# rfid_ctl3.net
KiCad netlist of a schematic drawn in EAGLE
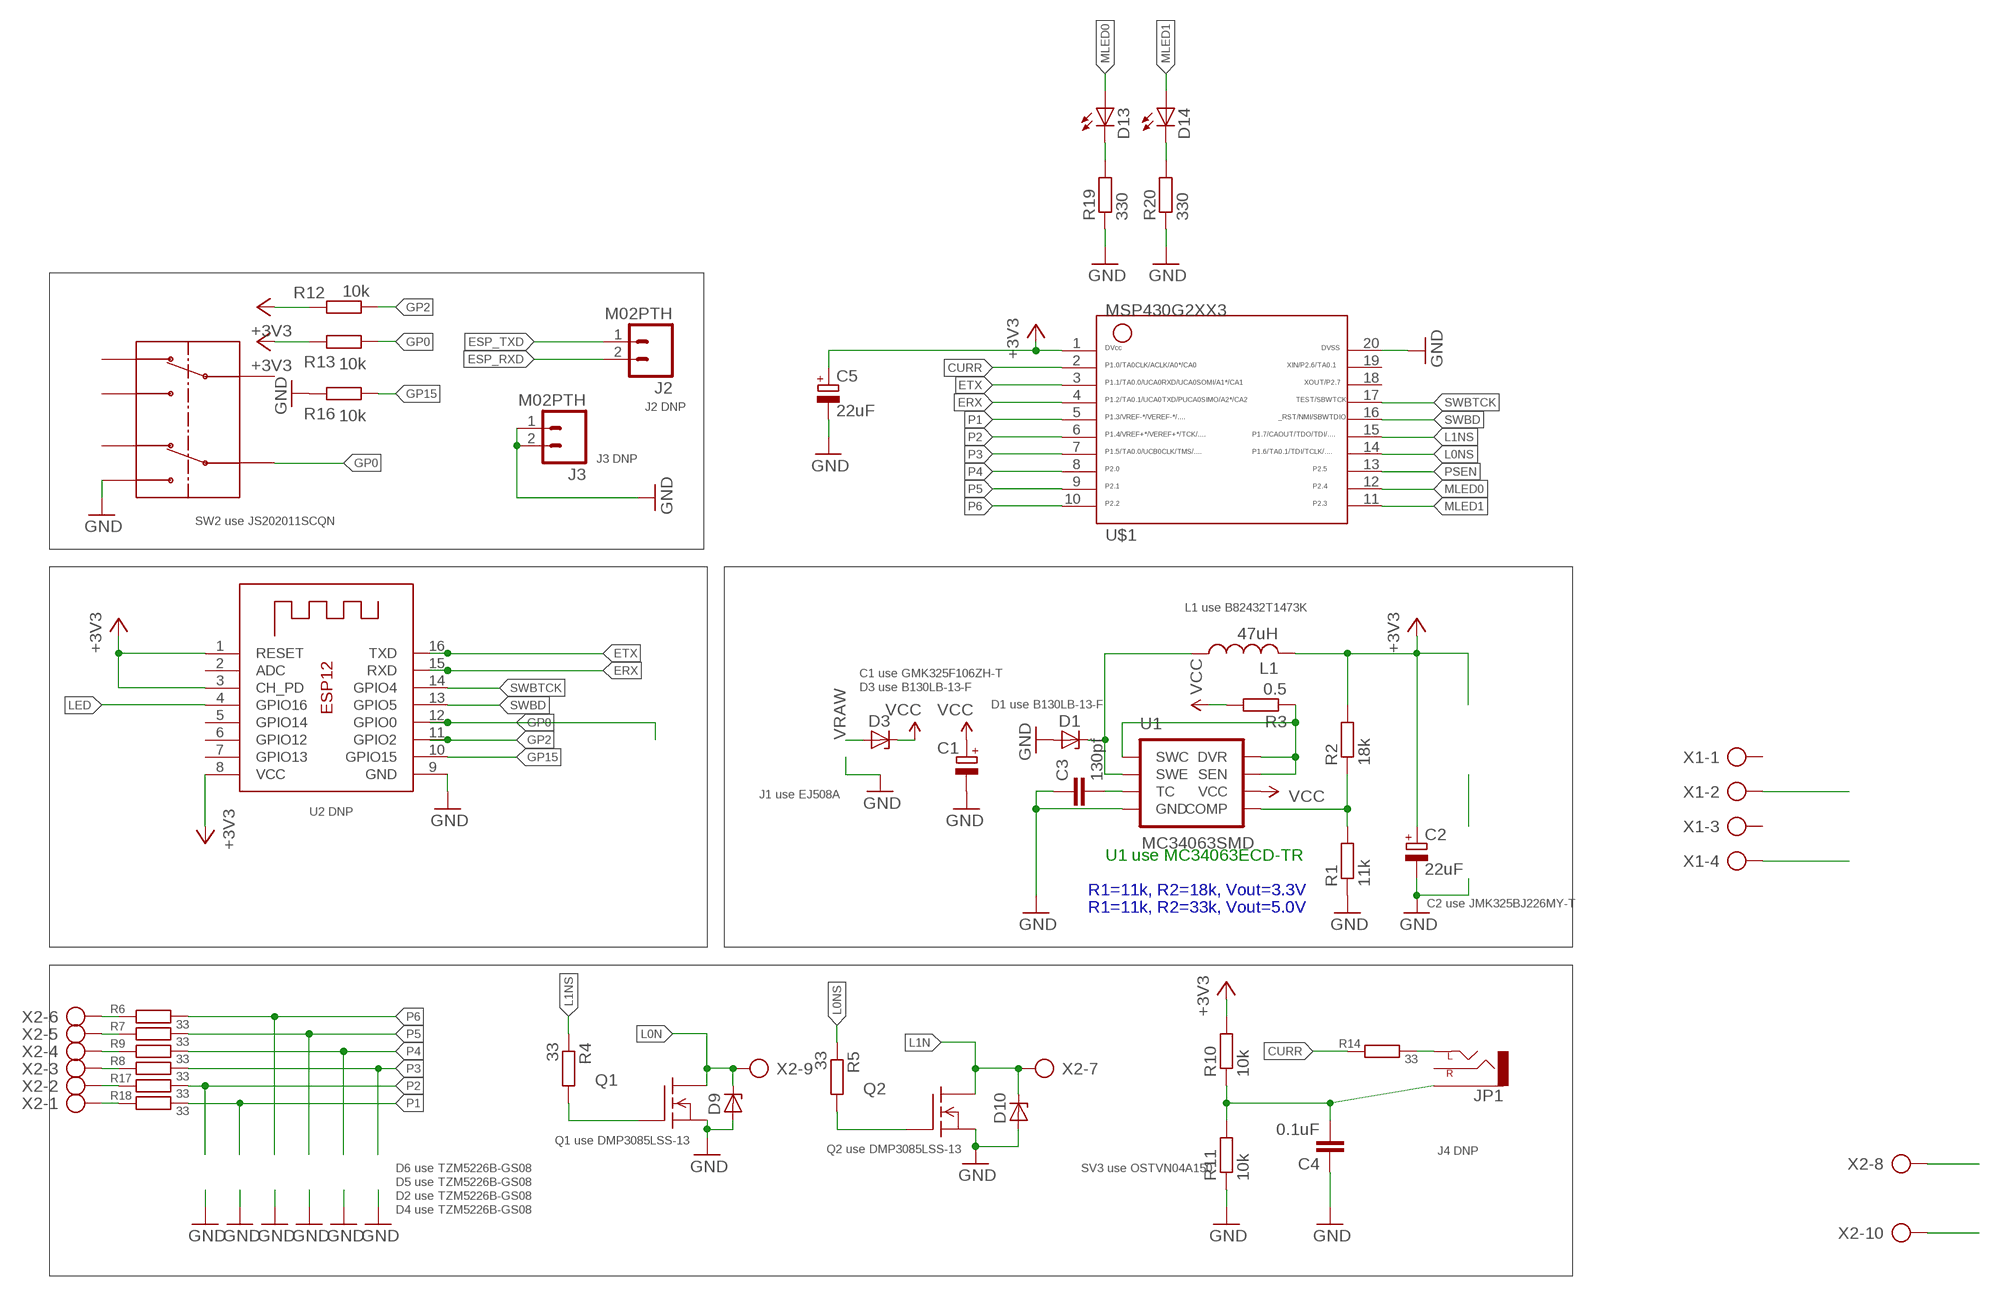
[diagram p0: schematic, sheet 1]

(export (version "E")
  (design (tool "Eeschema 10.0.6"))
  (components
    (comp (ref "C1")
      (value "CPOL-EUE2.5-7")
      (footprint "eagle-import:E2,5-7")
      (libsource (lib "eagle-import") (part "CPOL-EUE2.5-7"))
    )
    (comp (ref "C2")
      (value "22uF")
      (footprint "eagle-import:E2,5-7")
      (libsource (lib "eagle-import") (part "CPOL-EUE2.5-7"))
    )
    (comp (ref "C3")
      (value "130pf")
      (footprint "eagle-import:C1206")
      (libsource (lib "eagle-import") (part "C-EUC1206"))
    )
    (comp (ref "C4")
      (value "0.1uF")
      (footprint "eagle-import:C0603")
      (libsource (lib "eagle-import") (part "C-EUC0603"))
    )
    (comp (ref "C5")
      (value "22uF")
      (footprint "eagle-import:E1,8-4")
      (libsource (lib "eagle-import") (part "CPOL-EUE1.8-4"))
    )
    (comp (ref "D1")
      (value "ZENER-DIODESMB")
      (footprint "eagle-import:SMB")
      (libsource (lib "eagle-import") (part "ZENER-DIODESMB"))
    )
    (comp (ref "D3")
      (value "ZENER-DIODESMB")
      (footprint "eagle-import:SMB")
      (libsource (lib "eagle-import") (part "ZENER-DIODESMB"))
    )
    (comp (ref "D9")
      (value "ZENER-DIODESMB")
      (footprint "eagle-import:SMB")
      (libsource (lib "eagle-import") (part "ZENER-DIODESMB"))
    )
    (comp (ref "D10")
      (value "ZENER-DIODESMB")
      (footprint "eagle-import:SMB")
      (libsource (lib "eagle-import") (part "ZENER-DIODESMB"))
    )
    (comp (ref "D13")
      (value "LED5MM")
      (footprint "eagle-import:LED5MM")
      (libsource (lib "eagle-import") (part "LED5MM"))
    )
    (comp (ref "D14")
      (value "LED5MM")
      (footprint "eagle-import:LED5MM")
      (libsource (lib "eagle-import") (part "LED5MM"))
    )
    (comp (ref "J2")
      (value "M02PTH")
      (footprint "eagle-import:1X02")
      (libsource (lib "eagle-import") (part "M02PTH"))
    )
    (comp (ref "J3")
      (value "M02PTH")
      (footprint "eagle-import:1X02")
      (libsource (lib "eagle-import") (part "M02PTH"))
    )
    (comp (ref "JP1")
      (value "AUDIO-JACKSMD2")
      (footprint "eagle-import:AUDIO-JACK-3.5MM-SMD")
      (libsource (lib "eagle-import") (part "AUDIO-JACKSMD2"))
    )
    (comp (ref "L1")
      (value "47uH")
      (footprint "eagle-import:L1812")
      (libsource (lib "eagle-import") (part "L-USL1812"))
    )
    (comp (ref "Q1")
      (value "FDS5680")
      (footprint "eagle-import:SO-8")
      (libsource (lib "eagle-import") (part "FDS5680"))
    )
    (comp (ref "Q2")
      (value "FDS5680")
      (footprint "eagle-import:SO-8")
      (libsource (lib "eagle-import") (part "FDS5680"))
    )
    (comp (ref "R1")
      (value "11k")
      (footprint "eagle-import:R1206")
      (libsource (lib "eagle-import") (part "R-EU_R1206"))
    )
    (comp (ref "R2")
      (value "18k")
      (footprint "eagle-import:R1206")
      (libsource (lib "eagle-import") (part "R-EU_R1206"))
    )
    (comp (ref "R3")
      (value "0.5")
      (footprint "eagle-import:R1206")
      (libsource (lib "eagle-import") (part "R-EU_R1206"))
    )
    (comp (ref "R4")
      (value "33")
      (footprint "eagle-import:R1206")
      (libsource (lib "eagle-import") (part "R-EU_R1206"))
    )
    (comp (ref "R5")
      (value "33")
      (footprint "eagle-import:R1206")
      (libsource (lib "eagle-import") (part "R-EU_R1206"))
    )
    (comp (ref "R6")
      (value "33")
      (footprint "eagle-import:R1206")
      (libsource (lib "eagle-import") (part "R-EU_R1206"))
    )
    (comp (ref "R7")
      (value "33")
      (footprint "eagle-import:R1206")
      (libsource (lib "eagle-import") (part "R-EU_R1206"))
    )
    (comp (ref "R8")
      (value "33")
      (footprint "eagle-import:R1206")
      (libsource (lib "eagle-import") (part "R-EU_R1206"))
    )
    (comp (ref "R9")
      (value "33")
      (footprint "eagle-import:R1206")
      (libsource (lib "eagle-import") (part "R-EU_R1206"))
    )
    (comp (ref "R10")
      (value "10k")
      (footprint "eagle-import:R0603")
      (libsource (lib "eagle-import") (part "R-EU_R0603"))
    )
    (comp (ref "R11")
      (value "10k")
      (footprint "eagle-import:R0603")
      (libsource (lib "eagle-import") (part "R-EU_R0603"))
    )
    (comp (ref "R12")
      (value "10k")
      (footprint "eagle-import:R1206")
      (libsource (lib "eagle-import") (part "R-EU_R1206"))
    )
    (comp (ref "R13")
      (value "10k")
      (footprint "eagle-import:R1206")
      (libsource (lib "eagle-import") (part "R-EU_R1206"))
    )
    (comp (ref "R14")
      (value "33")
      (footprint "eagle-import:R1206")
      (libsource (lib "eagle-import") (part "R-EU_R1206"))
    )
    (comp (ref "R16")
      (value "10k")
      (footprint "eagle-import:R0603")
      (libsource (lib "eagle-import") (part "R-EU_R0603"))
    )
    (comp (ref "R17")
      (value "33")
      (footprint "eagle-import:R1206")
      (libsource (lib "eagle-import") (part "R-EU_R1206"))
    )
    (comp (ref "R18")
      (value "33")
      (footprint "eagle-import:R1206")
      (libsource (lib "eagle-import") (part "R-EU_R1206"))
    )
    (comp (ref "R19")
      (value "330")
      (footprint "eagle-import:R0805")
      (libsource (lib "eagle-import") (part "R-EU_R0805"))
    )
    (comp (ref "R20")
      (value "330")
      (footprint "eagle-import:R0805")
      (libsource (lib "eagle-import") (part "R-EU_R0805"))
    )
    (comp (ref "SW2")
      (value "L202011MS02Q")
      (footprint "eagle-import:SMT")
      (libsource (lib "eagle-import") (part "L202011MS02Q"))
    )
    (comp (ref "U$1")
      (value "G2XX3---N20")
      (footprint "eagle-import:N20")
      (libsource (lib "eagle-import") (part "G2XX3---N20"))
    )
    (comp (ref "U1")
      (value "MC34063SMD")
      (footprint "eagle-import:SO08")
      (libsource (lib "eagle-import") (part "MC34063SMD"))
    )
    (comp (ref "U2")
      (value "ESP-12")
      (footprint "eagle-import:ESP-12")
      (libsource (lib "eagle-import") (part "ESP-12"))
    )
    (comp (ref "X1")
      (value "AK300/4")
      (footprint "eagle-import:AK300_4")
      (libsource (lib "eagle-import") (part "AK300/4"))
    )
    (comp (ref "X2")
      (value "AK300/10")
      (footprint "eagle-import:AK300_10")
      (libsource (lib "eagle-import") (part "AK300/10"))
    )
  )
  (nets
    (net (code "1") (name "+3V3") (class "Default")
      (node (ref "C2") (pin "+") (pinfunction "+_+") (pintype "passive"))
      (node (ref "C5") (pin "+") (pinfunction "+_+") (pintype "passive"))
      (node (ref "L1") (pin "2") (pinfunction "2_2") (pintype "passive"))
      (node (ref "R10") (pin "2") (pinfunction "2_2") (pintype "passive"))
      (node (ref "R12") (pin "2") (pinfunction "2_2") (pintype "passive"))
      (node (ref "R13") (pin "2") (pinfunction "2_2") (pintype "passive"))
      (node (ref "R2") (pin "2") (pinfunction "2_2") (pintype "passive"))
      (node (ref "U$1") (pin "1") (pinfunction "1_1") (pintype "bidirectional"))
      (node (ref "U2") (pin "1") (pinfunction "RESET_1") (pintype "input"))
      (node (ref "U2") (pin "3") (pinfunction "CH_PD_3") (pintype "input"))
      (node (ref "U2") (pin "8") (pinfunction "VCC_8") (pintype "power_in"))
    )
    (net (code "2") (name "/VRAW") (class "Default")
      (node (ref "D3") (pin "A") (pinfunction "A_A") (pintype "passive"))
      (node (ref "X1") (pin "2") (pinfunction "KL_2") (pintype "passive"))
      (node (ref "X1") (pin "4") (pinfunction "KL_4") (pintype "passive"))
      (node (ref "X2") (pin "10") (pinfunction "KL_10") (pintype "passive"))
      (node (ref "X2") (pin "8") (pinfunction "KL_8") (pintype "passive"))
    )
    (net (code "3") (name "CURR") (class "Default")
      (node (ref "R14") (pin "1") (pinfunction "1_1") (pintype "passive"))
      (node (ref "U$1") (pin "2") (pinfunction "2_2") (pintype "bidirectional"))
    )
    (net (code "4") (name "ERX") (class "Default")
      (node (ref "U$1") (pin "4") (pinfunction "4_4") (pintype "bidirectional"))
      (node (ref "U2") (pin "15") (pinfunction "RXD_15") (pintype "input"))
    )
    (net (code "5") (name "ESP_RXD") (class "Default")
      (node (ref "J2") (pin "2") (pinfunction "2_2") (pintype "passive"))
    )
    (net (code "6") (name "ESP_TXD") (class "Default")
      (node (ref "J2") (pin "1") (pinfunction "1_1") (pintype "passive"))
    )
    (net (code "7") (name "ETX") (class "Default")
      (node (ref "U$1") (pin "3") (pinfunction "3_3") (pintype "bidirectional"))
      (node (ref "U2") (pin "16") (pinfunction "TXD_16") (pintype "output"))
    )
    (net (code "8") (name "GND") (class "Default")
      (node (ref "C1") (pin "-") (pinfunction "-_-") (pintype "passive"))
      (node (ref "C2") (pin "-") (pinfunction "-_-") (pintype "passive"))
      (node (ref "C3") (pin "1") (pinfunction "1_1") (pintype "passive"))
      (node (ref "C4") (pin "1") (pinfunction "1_1") (pintype "passive"))
      (node (ref "C5") (pin "-") (pinfunction "-_-") (pintype "passive"))
      (node (ref "D1") (pin "A") (pinfunction "A_A") (pintype "passive"))
      (node (ref "D10") (pin "A") (pinfunction "A_A") (pintype "passive"))
      (node (ref "D9") (pin "A") (pinfunction "A_A") (pintype "passive"))
      (node (ref "J3") (pin "1") (pinfunction "1_1") (pintype "passive"))
      (node (ref "J3") (pin "2") (pinfunction "2_2") (pintype "passive"))
      (node (ref "Q1") (pin "1") (pinfunction "S_1") (pintype "passive"))
      (node (ref "Q1") (pin "2") (pinfunction "S_2") (pintype "passive"))
      (node (ref "Q1") (pin "3") (pinfunction "S_3") (pintype "passive"))
      (node (ref "Q2") (pin "1") (pinfunction "S_1") (pintype "passive"))
      (node (ref "Q2") (pin "2") (pinfunction "S_2") (pintype "passive"))
      (node (ref "Q2") (pin "3") (pinfunction "S_3") (pintype "passive"))
      (node (ref "R1") (pin "1") (pinfunction "1_1") (pintype "passive"))
      (node (ref "R11") (pin "1") (pinfunction "1_1") (pintype "passive"))
      (node (ref "R16") (pin "2") (pinfunction "2_2") (pintype "passive"))
      (node (ref "R19") (pin "1") (pinfunction "1_1") (pintype "passive"))
      (node (ref "R20") (pin "1") (pinfunction "1_1") (pintype "passive"))
      (node (ref "SW2") (pin "B1") (pinfunction "B1_B1") (pintype "bidirectional"))
      (node (ref "U$1") (pin "20") (pinfunction "20_20") (pintype "bidirectional"))
      (node (ref "U1") (pin "4") (pinfunction "GND_4") (pintype "bidirectional"))
      (node (ref "U2") (pin "9") (pinfunction "GND_9") (pintype "power_in"))
    )
    (net (code "9") (name "GP0") (class "Default")
      (node (ref "R13") (pin "1") (pinfunction "1_1") (pintype "passive"))
      (node (ref "SW2") (pin "B") (pinfunction "B_B") (pintype "bidirectional"))
      (node (ref "U2") (pin "12") (pinfunction "GPIO0_12") (pintype "bidirectional"))
    )
    (net (code "10") (name "GP2") (class "Default")
      (node (ref "R12") (pin "1") (pinfunction "1_1") (pintype "passive"))
      (node (ref "U2") (pin "11") (pinfunction "GPIO2_11") (pintype "bidirectional"))
    )
    (net (code "11") (name "GP15") (class "Default")
      (node (ref "R16") (pin "1") (pinfunction "1_1") (pintype "passive"))
      (node (ref "U2") (pin "10") (pinfunction "GPIO15_10") (pintype "bidirectional"))
    )
    (net (code "12") (name "L0N") (class "Default")
      (node (ref "D9") (pin "C") (pinfunction "C_C") (pintype "passive"))
      (node (ref "Q1") (pin "5") (pinfunction "D_5") (pintype "passive"))
      (node (ref "Q1") (pin "6") (pinfunction "D_6") (pintype "passive"))
      (node (ref "Q1") (pin "7") (pinfunction "D_7") (pintype "passive"))
      (node (ref "Q1") (pin "8") (pinfunction "D_8") (pintype "passive"))
      (node (ref "X2") (pin "9") (pinfunction "KL_9") (pintype "passive"))
    )
    (net (code "13") (name "L0NS") (class "Default")
      (node (ref "R5") (pin "1") (pinfunction "1_1") (pintype "passive"))
      (node (ref "U$1") (pin "14") (pinfunction "14_14") (pintype "bidirectional"))
    )
    (net (code "14") (name "L1N") (class "Default")
      (node (ref "D10") (pin "C") (pinfunction "C_C") (pintype "passive"))
      (node (ref "Q2") (pin "5") (pinfunction "D_5") (pintype "passive"))
      (node (ref "Q2") (pin "6") (pinfunction "D_6") (pintype "passive"))
      (node (ref "Q2") (pin "7") (pinfunction "D_7") (pintype "passive"))
      (node (ref "Q2") (pin "8") (pinfunction "D_8") (pintype "passive"))
      (node (ref "X2") (pin "7") (pinfunction "KL_7") (pintype "passive"))
    )
    (net (code "15") (name "L1NS") (class "Default")
      (node (ref "R4") (pin "1") (pinfunction "1_1") (pintype "passive"))
      (node (ref "U$1") (pin "15") (pinfunction "15_15") (pintype "bidirectional"))
    )
    (net (code "16") (name "LED") (class "Default")
      (node (ref "U2") (pin "4") (pinfunction "GPIO16_4") (pintype "bidirectional"))
    )
    (net (code "17") (name "MLED0") (class "Default")
      (node (ref "D13") (pin "A") (pinfunction "A_A") (pintype "passive"))
      (node (ref "U$1") (pin "12") (pinfunction "12_12") (pintype "bidirectional"))
    )
    (net (code "18") (name "MLED1") (class "Default")
      (node (ref "D14") (pin "A") (pinfunction "A_A") (pintype "passive"))
      (node (ref "U$1") (pin "11") (pinfunction "11_11") (pintype "bidirectional"))
    )
    (net (code "19") (name "Net-(C4-Pad2)") (class "Default")
      (node (ref "C4") (pin "2") (pinfunction "2_2") (pintype "passive"))
      (node (ref "JP1") (pin "SLEEVE") (pinfunction "SLEEVE_SLEEVE") (pintype "bidirectional"))
      (node (ref "R10") (pin "1") (pinfunction "1_1") (pintype "passive"))
      (node (ref "R11") (pin "2") (pinfunction "2_2") (pintype "passive"))
    )
    (net (code "20") (name "Net-(D13-C)") (class "Default")
      (node (ref "D13") (pin "K") (pinfunction "C_K") (pintype "passive"))
      (node (ref "R19") (pin "2") (pinfunction "2_2") (pintype "passive"))
    )
    (net (code "21") (name "Net-(D14-C)") (class "Default")
      (node (ref "D14") (pin "K") (pinfunction "C_K") (pintype "passive"))
      (node (ref "R20") (pin "2") (pinfunction "2_2") (pintype "passive"))
    )
    (net (code "22") (name "Net-(JP1-LEFT)") (class "Default")
      (node (ref "JP1") (pin "TIP") (pinfunction "LEFT_TIP") (pintype "bidirectional"))
      (node (ref "R14") (pin "2") (pinfunction "2_2") (pintype "passive"))
    )
    (net (code "23") (name "Net-(Q1-G)") (class "Default")
      (node (ref "Q1") (pin "4") (pinfunction "G_4") (pintype "passive"))
      (node (ref "R4") (pin "2") (pinfunction "2_2") (pintype "passive"))
    )
    (net (code "24") (name "Net-(Q2-G)") (class "Default")
      (node (ref "Q2") (pin "4") (pinfunction "G_4") (pintype "passive"))
      (node (ref "R5") (pin "2") (pinfunction "2_2") (pintype "passive"))
    )
    (net (code "25") (name "Net-(U1-COMP)") (class "Default")
      (node (ref "R1") (pin "2") (pinfunction "2_2") (pintype "passive"))
      (node (ref "R2") (pin "1") (pinfunction "1_1") (pintype "passive"))
      (node (ref "U1") (pin "5") (pinfunction "COMP_5") (pintype "bidirectional"))
    )
    (net (code "26") (name "Net-(U1-DVR)") (class "Default")
      (node (ref "R3") (pin "1") (pinfunction "1_1") (pintype "passive"))
      (node (ref "U1") (pin "1") (pinfunction "SWC_1") (pintype "bidirectional"))
      (node (ref "U1") (pin "7") (pinfunction "SEN_7") (pintype "bidirectional"))
      (node (ref "U1") (pin "8") (pinfunction "DVR_8") (pintype "bidirectional"))
    )
    (net (code "27") (name "Net-(U1-SWE)") (class "Default")
      (node (ref "D1") (pin "C") (pinfunction "C_C") (pintype "passive"))
      (node (ref "L1") (pin "1") (pinfunction "1_1") (pintype "passive"))
      (node (ref "U1") (pin "2") (pinfunction "SWE_2") (pintype "bidirectional"))
    )
    (net (code "28") (name "Net-(U1-TC)") (class "Default")
      (node (ref "C3") (pin "2") (pinfunction "2_2") (pintype "passive"))
      (node (ref "U1") (pin "3") (pinfunction "TC_3") (pintype "bidirectional"))
    )
    (net (code "29") (name "Net-(X2A-KL)") (class "Default")
      (node (ref "R18") (pin "1") (pinfunction "1_1") (pintype "passive"))
      (node (ref "X2") (pin "1") (pinfunction "KL_1") (pintype "passive"))
    )
    (net (code "30") (name "Net-(X2C-KL)") (class "Default")
      (node (ref "R17") (pin "1") (pinfunction "1_1") (pintype "passive"))
      (node (ref "X2") (pin "2") (pinfunction "KL_2") (pintype "passive"))
    )
    (net (code "31") (name "Net-(X2D-KL)") (class "Default")
      (node (ref "R9") (pin "1") (pinfunction "1_1") (pintype "passive"))
      (node (ref "X2") (pin "3") (pinfunction "KL_3") (pintype "passive"))
    )
    (net (code "32") (name "Net-(X2E-KL)") (class "Default")
      (node (ref "R8") (pin "1") (pinfunction "1_1") (pintype "passive"))
      (node (ref "X2") (pin "4") (pinfunction "KL_4") (pintype "passive"))
    )
    (net (code "33") (name "Net-(X2F-KL)") (class "Default")
      (node (ref "R7") (pin "1") (pinfunction "1_1") (pintype "passive"))
      (node (ref "X2") (pin "5") (pinfunction "KL_5") (pintype "passive"))
    )
    (net (code "34") (name "Net-(X2G-KL)") (class "Default")
      (node (ref "R6") (pin "1") (pinfunction "1_1") (pintype "passive"))
      (node (ref "X2") (pin "6") (pinfunction "KL_6") (pintype "passive"))
    )
    (net (code "35") (name "P1") (class "Default")
      (node (ref "R18") (pin "2") (pinfunction "2_2") (pintype "passive"))
      (node (ref "U$1") (pin "5") (pinfunction "5_5") (pintype "bidirectional"))
    )
    (net (code "36") (name "P2") (class "Default")
      (node (ref "R17") (pin "2") (pinfunction "2_2") (pintype "passive"))
      (node (ref "U$1") (pin "6") (pinfunction "6_6") (pintype "bidirectional"))
    )
    (net (code "37") (name "P3") (class "Default")
      (node (ref "R9") (pin "2") (pinfunction "2_2") (pintype "passive"))
      (node (ref "U$1") (pin "7") (pinfunction "7_7") (pintype "bidirectional"))
    )
    (net (code "38") (name "P4") (class "Default")
      (node (ref "R8") (pin "2") (pinfunction "2_2") (pintype "passive"))
      (node (ref "U$1") (pin "8") (pinfunction "8_8") (pintype "bidirectional"))
    )
    (net (code "39") (name "P5") (class "Default")
      (node (ref "R7") (pin "2") (pinfunction "2_2") (pintype "passive"))
      (node (ref "U$1") (pin "9") (pinfunction "9_9") (pintype "bidirectional"))
    )
    (net (code "40") (name "P6") (class "Default")
      (node (ref "R6") (pin "2") (pinfunction "2_2") (pintype "passive"))
      (node (ref "U$1") (pin "10") (pinfunction "10_10") (pintype "bidirectional"))
    )
    (net (code "41") (name "PSEN") (class "Default")
      (node (ref "U$1") (pin "13") (pinfunction "13_13") (pintype "bidirectional"))
    )
    (net (code "42") (name "SWBD") (class "Default")
      (node (ref "U$1") (pin "16") (pinfunction "16_16") (pintype "bidirectional"))
      (node (ref "U2") (pin "13") (pinfunction "GPIO5_13") (pintype "bidirectional"))
    )
    (net (code "43") (name "SWBTCK") (class "Default")
      (node (ref "U$1") (pin "17") (pinfunction "17_17") (pintype "bidirectional"))
      (node (ref "U2") (pin "14") (pinfunction "GPIO4_14") (pintype "bidirectional"))
    )
    (net (code "44") (name "VCC") (class "Default")
      (node (ref "C1") (pin "+") (pinfunction "+_+") (pintype "passive"))
      (node (ref "D3") (pin "C") (pinfunction "C_C") (pintype "passive"))
      (node (ref "R3") (pin "2") (pinfunction "2_2") (pintype "passive"))
      (node (ref "U1") (pin "6") (pinfunction "VCC_6") (pintype "bidirectional"))
    )
    (net (code "45") (name "unconnected-(JP1-RIGHT-PadRING)") (class "Default")
      (node (ref "JP1") (pin "RING") (pinfunction "RIGHT_RING") (pintype "bidirectional"))
    )
    (net (code "46") (name "unconnected-(SW2-PadA)") (class "Default")
      (node (ref "SW2") (pin "A") (pinfunction "A_A") (pintype "bidirectional"))
    )
    (net (code "47") (name "unconnected-(SW2-PadA1)") (class "Default")
      (node (ref "SW2") (pin "A1") (pinfunction "A1_A1") (pintype "bidirectional"))
    )
    (net (code "48") (name "unconnected-(SW2-PadA2)") (class "Default")
      (node (ref "SW2") (pin "A2") (pinfunction "A2_A2") (pintype "bidirectional"))
    )
    (net (code "49") (name "unconnected-(SW2-PadB2)") (class "Default")
      (node (ref "SW2") (pin "B2") (pinfunction "B2_B2") (pintype "bidirectional"))
    )
    (net (code "50") (name "unconnected-(U$1-Pad18)") (class "Default")
      (node (ref "U$1") (pin "18") (pinfunction "18_18") (pintype "bidirectional"))
    )
    (net (code "51") (name "unconnected-(U$1-Pad19)") (class "Default")
      (node (ref "U$1") (pin "19") (pinfunction "19_19") (pintype "bidirectional"))
    )
    (net (code "52") (name "unconnected-(U2-ADC-Pad2)") (class "Default")
      (node (ref "U2") (pin "2") (pinfunction "ADC_2") (pintype "passive"))
    )
    (net (code "53") (name "unconnected-(U2-GPIO12-Pad6)") (class "Default")
      (node (ref "U2") (pin "6") (pinfunction "GPIO12_6") (pintype "bidirectional"))
    )
    (net (code "54") (name "unconnected-(U2-GPIO13-Pad7)") (class "Default")
      (node (ref "U2") (pin "7") (pinfunction "GPIO13_7") (pintype "bidirectional"))
    )
    (net (code "55") (name "unconnected-(U2-GPIO14-Pad5)") (class "Default")
      (node (ref "U2") (pin "5") (pinfunction "GPIO14_5") (pintype "bidirectional"))
    )
    (net (code "56") (name "unconnected-(X1A-KL-Pad1)") (class "Default")
      (node (ref "X1") (pin "1") (pinfunction "KL_1") (pintype "passive"))
    )
    (net (code "57") (name "unconnected-(X1C-KL-Pad3)") (class "Default")
      (node (ref "X1") (pin "3") (pinfunction "KL_3") (pintype "passive"))
    )
  )
)
